# wiring_diagram.net
KiCad netlist of a schematic drawn in EAGLE
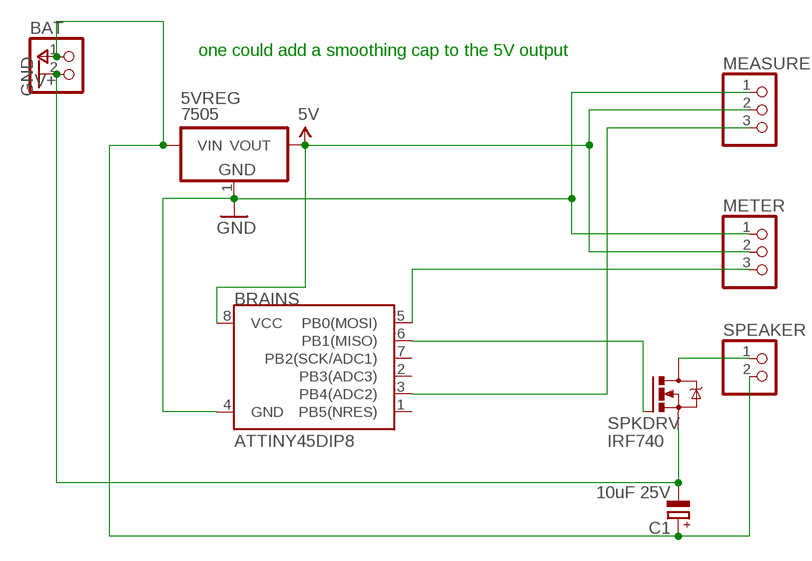
[diagram p0: schematic, sheet 1]

(export (version "E")
  (design (tool "Eeschema 10.0.6"))
  (components
    (comp (ref "5VREG")
      (value "7505")
      (footprint "eagle-import:TO-220V")
      (libsource (lib "eagle-import") (part "IC_VREG_3PINS-TO-220"))
    )
    (comp (ref "BAT")
      (value "PINHD-1X2")
      (footprint "eagle-import:1X02")
      (libsource (lib "eagle-import") (part "PINHD-1X2"))
    )
    (comp (ref "BRAINS")
      (value "ATTINY45DIP8")
      (footprint "eagle-import:DIP08")
      (libsource (lib "eagle-import") (part "ATTINY45DIP8"))
    )
    (comp (ref "C1")
      (value "10uF 25V")
      (footprint "eagle-import:E2-4")
      (libsource (lib "eagle-import") (part "CPOL-EUE2-4"))
    )
    (comp (ref "MEASURE")
      (value "PINHD-1X3")
      (footprint "eagle-import:1X03")
      (libsource (lib "eagle-import") (part "PINHD-1X3"))
    )
    (comp (ref "METER")
      (value "PINHD-1X3")
      (footprint "eagle-import:1X03")
      (libsource (lib "eagle-import") (part "PINHD-1X3"))
    )
    (comp (ref "SPEAKER")
      (value "PINHD-1X2")
      (footprint "eagle-import:1X02")
      (libsource (lib "eagle-import") (part "PINHD-1X2"))
    )
    (comp (ref "SPKDRV")
      (value "IRF740")
      (footprint "eagle-import:TO220BV")
      (libsource (lib "eagle-import") (part "IRF740"))
    )
  )
  (nets
    (net (code "1") (name "5V") (class "Default")
      (node (ref "5VREG") (pin "2") (pinfunction "VOUT_2") (pintype "bidirectional"))
      (node (ref "BRAINS") (pin "8") (pinfunction "VCC_8") (pintype "bidirectional"))
      (node (ref "MEASURE") (pin "2") (pinfunction "2_2") (pintype "passive"))
      (node (ref "METER") (pin "2") (pinfunction "2_2") (pintype "passive"))
    )
    (net (code "2") (name "GND") (class "Default")
      (node (ref "5VREG") (pin "1") (pinfunction "GND_1") (pintype "bidirectional"))
      (node (ref "BAT") (pin "2") (pinfunction "2_2") (pintype "passive"))
      (node (ref "BRAINS") (pin "4") (pinfunction "GND_4") (pintype "bidirectional"))
      (node (ref "C1") (pin "-") (pinfunction "-_-") (pintype "passive"))
      (node (ref "MEASURE") (pin "1") (pinfunction "1_1") (pintype "passive"))
      (node (ref "METER") (pin "1") (pinfunction "1_1") (pintype "passive"))
      (node (ref "SPKDRV") (pin "S") (pinfunction "S_S") (pintype "passive"))
    )
    (net (code "3") (name "Net-(BRAINS-PB0(MOSI))") (class "Default")
      (node (ref "BRAINS") (pin "5") (pinfunction "PB0(MOSI)_5") (pintype "bidirectional"))
      (node (ref "METER") (pin "3") (pinfunction "3_3") (pintype "passive"))
    )
    (net (code "4") (name "Net-(BRAINS-PB1(MISO))") (class "Default")
      (node (ref "BRAINS") (pin "6") (pinfunction "PB1(MISO)_6") (pintype "bidirectional"))
      (node (ref "SPKDRV") (pin "G") (pinfunction "G_G") (pintype "passive"))
    )
    (net (code "5") (name "Net-(BRAINS-PB4(ADC2))") (class "Default")
      (node (ref "BRAINS") (pin "3") (pinfunction "PB4(ADC2)_3") (pintype "bidirectional"))
      (node (ref "MEASURE") (pin "3") (pinfunction "3_3") (pintype "passive"))
    )
    (net (code "6") (name "Net-(SPEAKER-Pad1)") (class "Default")
      (node (ref "SPEAKER") (pin "1") (pinfunction "1_1") (pintype "passive"))
      (node (ref "SPKDRV") (pin "D") (pinfunction "D_D") (pintype "passive"))
    )
    (net (code "7") (name "V+") (class "Default")
      (node (ref "5VREG") (pin "3") (pinfunction "VIN_3") (pintype "bidirectional"))
      (node (ref "BAT") (pin "1") (pinfunction "1_1") (pintype "passive"))
      (node (ref "C1") (pin "+") (pinfunction "+_+") (pintype "passive"))
      (node (ref "SPEAKER") (pin "2") (pinfunction "2_2") (pintype "passive"))
    )
    (net (code "8") (name "unconnected-(BRAINS-PB2(SCK{slash}ADC1)-Pad7)") (class "Default")
      (node (ref "BRAINS") (pin "7") (pinfunction "PB2(SCK/ADC1)_7") (pintype "bidirectional"))
    )
    (net (code "9") (name "unconnected-(BRAINS-PB3(ADC3)-Pad2)") (class "Default")
      (node (ref "BRAINS") (pin "2") (pinfunction "PB3(ADC3)_2") (pintype "bidirectional"))
    )
    (net (code "10") (name "unconnected-(BRAINS-PB5(NRES)-Pad1)") (class "Default")
      (node (ref "BRAINS") (pin "1") (pinfunction "PB5(NRES)_1") (pintype "bidirectional"))
    )
  )
)
